# lt3750_test.net
KiCad netlist of a schematic drawn in EAGLE
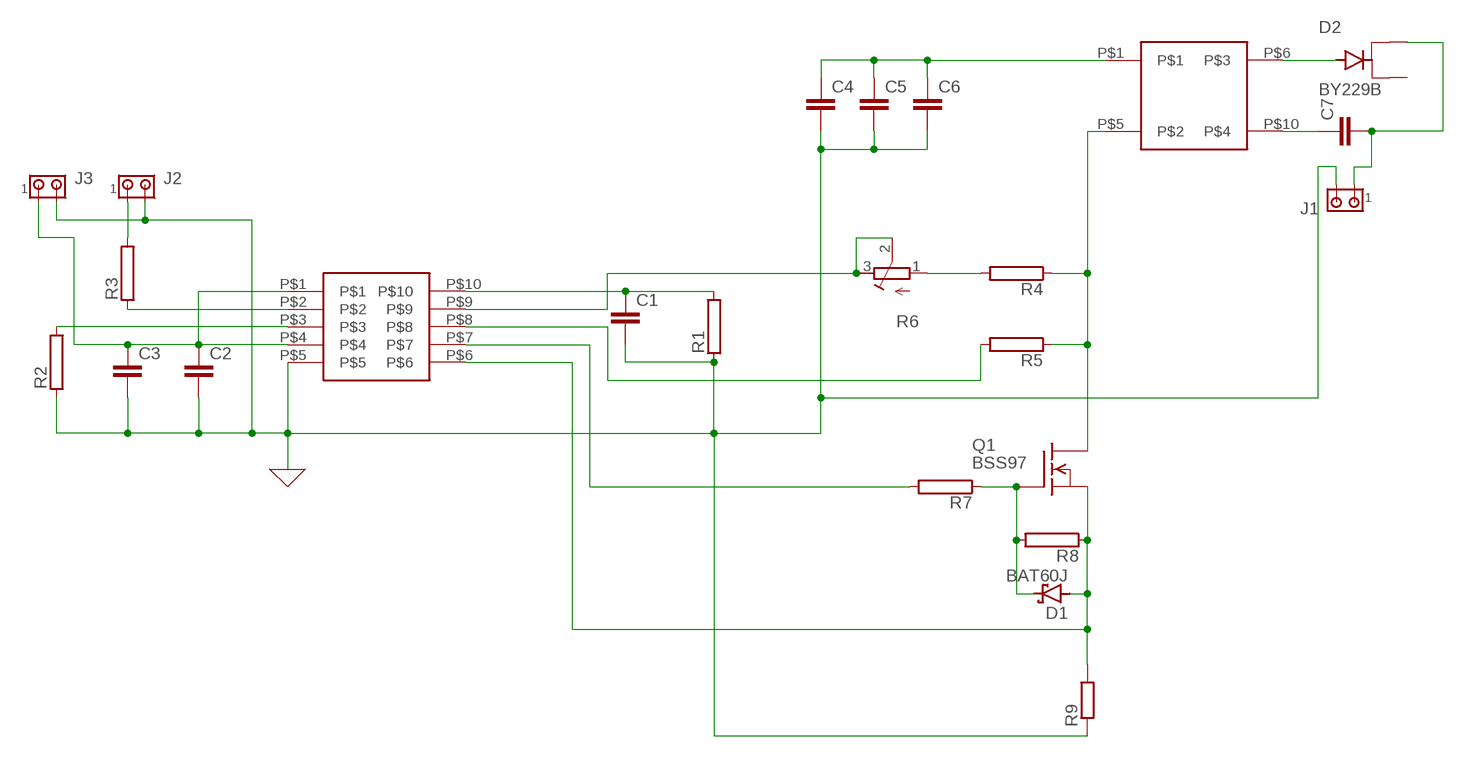
[diagram p0: schematic, sheet 1]

(export (version "E")
  (design (tool "Eeschema 10.0.6"))
  (components
    (comp (ref "C1")
      (value "C5/3")
      (footprint "eagle-import:C5B3")
      (libsource (lib "eagle-import") (part "C5/3"))
    )
    (comp (ref "C2")
      (value "C5/3")
      (footprint "eagle-import:C5B3")
      (libsource (lib "eagle-import") (part "C5/3"))
    )
    (comp (ref "C3")
      (value "C5/3")
      (footprint "eagle-import:C5B3")
      (libsource (lib "eagle-import") (part "C5/3"))
    )
    (comp (ref "C4")
      (value "C5/3")
      (footprint "eagle-import:C5B3")
      (libsource (lib "eagle-import") (part "C5/3"))
    )
    (comp (ref "C5")
      (value "C5/3")
      (footprint "eagle-import:C5B3")
      (libsource (lib "eagle-import") (part "C5/3"))
    )
    (comp (ref "C6")
      (value "C5/3")
      (footprint "eagle-import:C5B3")
      (libsource (lib "eagle-import") (part "C5/3"))
    )
    (comp (ref "C7")
      (value "C5/3")
      (footprint "eagle-import:C5B3")
      (libsource (lib "eagle-import") (part "C5/3"))
    )
    (comp (ref "D1")
      (value "BAT60J")
      (footprint "eagle-import:SOD323_ST")
      (libsource (lib "eagle-import") (part "BAT60J"))
    )
    (comp (ref "D2")
      (value "BY229B")
      (footprint "eagle-import:TO263AB")
      (libsource (lib "eagle-import") (part "BY229B"))
    )
    (comp (ref "J1")
      (value "MTA02-100")
      (footprint "eagle-import:10X02MTA")
      (libsource (lib "eagle-import") (part "MTA02-100"))
    )
    (comp (ref "J2")
      (value "MTA02-100")
      (footprint "eagle-import:10X02MTA")
      (libsource (lib "eagle-import") (part "MTA02-100"))
    )
    (comp (ref "J3")
      (value "MTA02-100")
      (footprint "eagle-import:10X02MTA")
      (libsource (lib "eagle-import") (part "MTA02-100"))
    )
    (comp (ref "Q1")
      (value "BSS97")
      (footprint "eagle-import:TO202")
      (libsource (lib "eagle-import") (part "BSS97"))
    )
    (comp (ref "R1")
      (value "RAC01")
      (footprint "eagle-import:AC01")
      (libsource (lib "eagle-import") (part "RAC01"))
    )
    (comp (ref "R2")
      (value "RAC01")
      (footprint "eagle-import:AC01")
      (libsource (lib "eagle-import") (part "RAC01"))
    )
    (comp (ref "R3")
      (value "RAC01")
      (footprint "eagle-import:AC01")
      (libsource (lib "eagle-import") (part "RAC01"))
    )
    (comp (ref "R4")
      (value "RAC01")
      (footprint "eagle-import:AC01")
      (libsource (lib "eagle-import") (part "RAC01"))
    )
    (comp (ref "R5")
      (value "RAC01")
      (footprint "eagle-import:AC01")
      (libsource (lib "eagle-import") (part "RAC01"))
    )
    (comp (ref "R6")
      (value "R-TRIMM64X")
      (footprint "eagle-import:RTRIM64X")
      (libsource (lib "eagle-import") (part "R-TRIMM64X"))
    )
    (comp (ref "R7")
      (value "RAC01")
      (footprint "eagle-import:AC01")
      (libsource (lib "eagle-import") (part "RAC01"))
    )
    (comp (ref "R8")
      (value "RAC01")
      (footprint "eagle-import:AC01")
      (libsource (lib "eagle-import") (part "RAC01"))
    )
    (comp (ref "R9")
      (value "SMK")
      (footprint "eagle-import:SMK")
      (libsource (lib "eagle-import") (part "SMK"))
    )
    (comp (ref "U$1")
      (value "LT3750")
      (footprint "eagle-import:LT3750")
      (libsource (lib "eagle-import") (part "LT3750"))
    )
    (comp (ref "U$2")
      (value "32052")
      (footprint "eagle-import:32052")
      (libsource (lib "eagle-import") (part "32052"))
    )
  )
  (nets
    (net (code "1") (name "GND") (class "Default")
      (node (ref "C1") (pin "2") (pinfunction "2_2") (pintype "passive"))
      (node (ref "C2") (pin "2") (pinfunction "2_2") (pintype "passive"))
      (node (ref "C3") (pin "2") (pinfunction "2_2") (pintype "passive"))
      (node (ref "C4") (pin "2") (pinfunction "2_2") (pintype "passive"))
      (node (ref "C5") (pin "2") (pinfunction "2_2") (pintype "passive"))
      (node (ref "C6") (pin "2") (pinfunction "2_2") (pintype "passive"))
      (node (ref "J1") (pin "2") (pinfunction "2_2") (pintype "passive"))
      (node (ref "J2") (pin "2") (pinfunction "2_2") (pintype "passive"))
      (node (ref "J3") (pin "2") (pinfunction "2_2") (pintype "passive"))
      (node (ref "R1") (pin "1") (pinfunction "1_1") (pintype "passive"))
      (node (ref "R2") (pin "1") (pinfunction "1_1") (pintype "passive"))
      (node (ref "R9") (pin "2") (pinfunction "2_2") (pintype "passive"))
      (node (ref "U$1") (pin "P$5") (pinfunction "P$5_P$5") (pintype "bidirectional"))
    )
    (net (code "2") (name "Net-(C1-Pad1)") (class "Default")
      (node (ref "C1") (pin "1") (pinfunction "1_1") (pintype "passive"))
      (node (ref "R1") (pin "2") (pinfunction "2_2") (pintype "passive"))
      (node (ref "U$1") (pin "P$10") (pinfunction "P$10_P$10") (pintype "bidirectional"))
    )
    (net (code "3") (name "Net-(C2-Pad1)") (class "Default")
      (node (ref "C2") (pin "1") (pinfunction "1_1") (pintype "passive"))
      (node (ref "C3") (pin "1") (pinfunction "1_1") (pintype "passive"))
      (node (ref "J3") (pin "1") (pinfunction "1_1") (pintype "passive"))
      (node (ref "U$1") (pin "P$1") (pinfunction "P$1_P$1") (pintype "bidirectional"))
      (node (ref "U$1") (pin "P$4") (pinfunction "P$4_P$4") (pintype "bidirectional"))
    )
    (net (code "4") (name "Net-(C4-Pad1)") (class "Default")
      (node (ref "C4") (pin "1") (pinfunction "1_1") (pintype "passive"))
      (node (ref "C5") (pin "1") (pinfunction "1_1") (pintype "passive"))
      (node (ref "C6") (pin "1") (pinfunction "1_1") (pintype "passive"))
      (node (ref "U$2") (pin "P$1") (pinfunction "P$1_P$1") (pintype "bidirectional"))
    )
    (net (code "5") (name "Net-(C7-Pad2)") (class "Default")
      (node (ref "C7") (pin "2") (pinfunction "2_2") (pintype "passive"))
      (node (ref "D2") (pin "1") (pinfunction "1_1") (pintype "passive"))
      (node (ref "J1") (pin "1") (pinfunction "1_1") (pintype "passive"))
    )
    (net (code "6") (name "Net-(J2-Pad1)") (class "Default")
      (node (ref "J2") (pin "1") (pinfunction "1_1") (pintype "passive"))
      (node (ref "R3") (pin "2") (pinfunction "2_2") (pintype "passive"))
    )
    (net (code "7") (name "Net-(Q1-D)") (class "Default")
      (node (ref "Q1") (pin "2") (pinfunction "D_2") (pintype "passive"))
      (node (ref "R4") (pin "1") (pinfunction "1_1") (pintype "passive"))
      (node (ref "R5") (pin "1") (pinfunction "1_1") (pintype "passive"))
      (node (ref "U$2") (pin "P$5") (pinfunction "P$2_P$5") (pintype "bidirectional"))
    )
    (net (code "8") (name "Net-(Q1-G)") (class "Default")
      (node (ref "D1") (pin "C") (pinfunction "C_C") (pintype "passive"))
      (node (ref "Q1") (pin "3") (pinfunction "G_3") (pintype "passive"))
      (node (ref "R7") (pin "1") (pinfunction "1_1") (pintype "passive"))
      (node (ref "R8") (pin "2") (pinfunction "2_2") (pintype "passive"))
    )
    (net (code "9") (name "Net-(Q1-S)") (class "Default")
      (node (ref "D1") (pin "A") (pinfunction "A_A") (pintype "passive"))
      (node (ref "Q1") (pin "1") (pinfunction "S_1") (pintype "passive"))
      (node (ref "R8") (pin "1") (pinfunction "1_1") (pintype "passive"))
      (node (ref "R9") (pin "1") (pinfunction "1_1") (pintype "passive"))
      (node (ref "U$1") (pin "P$6") (pinfunction "P$6_P$6") (pintype "bidirectional"))
    )
    (net (code "10") (name "Net-(R2-Pad2)") (class "Default")
      (node (ref "R2") (pin "2") (pinfunction "2_2") (pintype "passive"))
      (node (ref "U$1") (pin "P$3") (pinfunction "P$3_P$3") (pintype "bidirectional"))
    )
    (net (code "11") (name "Net-(R3-Pad1)") (class "Default")
      (node (ref "R3") (pin "1") (pinfunction "1_1") (pintype "passive"))
      (node (ref "U$1") (pin "P$2") (pinfunction "P$2_P$2") (pintype "bidirectional"))
    )
    (net (code "12") (name "Net-(R5-Pad2)") (class "Default")
      (node (ref "R5") (pin "2") (pinfunction "2_2") (pintype "passive"))
      (node (ref "U$1") (pin "P$8") (pinfunction "P$8_P$8") (pintype "bidirectional"))
    )
    (net (code "13") (name "Net-(R6-A)") (class "Default")
      (node (ref "R4") (pin "2") (pinfunction "2_2") (pintype "passive"))
      (node (ref "R6") (pin "1") (pinfunction "A_1") (pintype "passive"))
    )
    (net (code "14") (name "Net-(R6-E)") (class "Default")
      (node (ref "R6") (pin "2") (pinfunction "S_2") (pintype "passive"))
      (node (ref "R6") (pin "3") (pinfunction "E_3") (pintype "passive"))
      (node (ref "U$1") (pin "P$9") (pinfunction "P$9_P$9") (pintype "bidirectional"))
    )
    (net (code "15") (name "Net-(R7-Pad2)") (class "Default")
      (node (ref "R7") (pin "2") (pinfunction "2_2") (pintype "passive"))
      (node (ref "U$1") (pin "P$7") (pinfunction "P$7_P$7") (pintype "bidirectional"))
    )
    (net (code "16") (name "Net-(U$2-P$3)") (class "Default")
      (node (ref "D2") (pin "2") (pinfunction "2_2") (pintype "passive"))
      (node (ref "U$2") (pin "P$6") (pinfunction "P$3_P$6") (pintype "bidirectional"))
    )
    (net (code "17") (name "Net-(U$2-P$4)") (class "Default")
      (node (ref "C7") (pin "1") (pinfunction "1_1") (pintype "passive"))
      (node (ref "U$2") (pin "P$10") (pinfunction "P$4_P$10") (pintype "bidirectional"))
    )
    (net (code "18") (name "unconnected-(D2-PadK)") (class "Default")
      (node (ref "D2") (pin "K") (pinfunction "K_K") (pintype "passive"))
    )
  )
)
